# placa_eagle_1_1.net
KiCad netlist of a schematic drawn in EAGLE
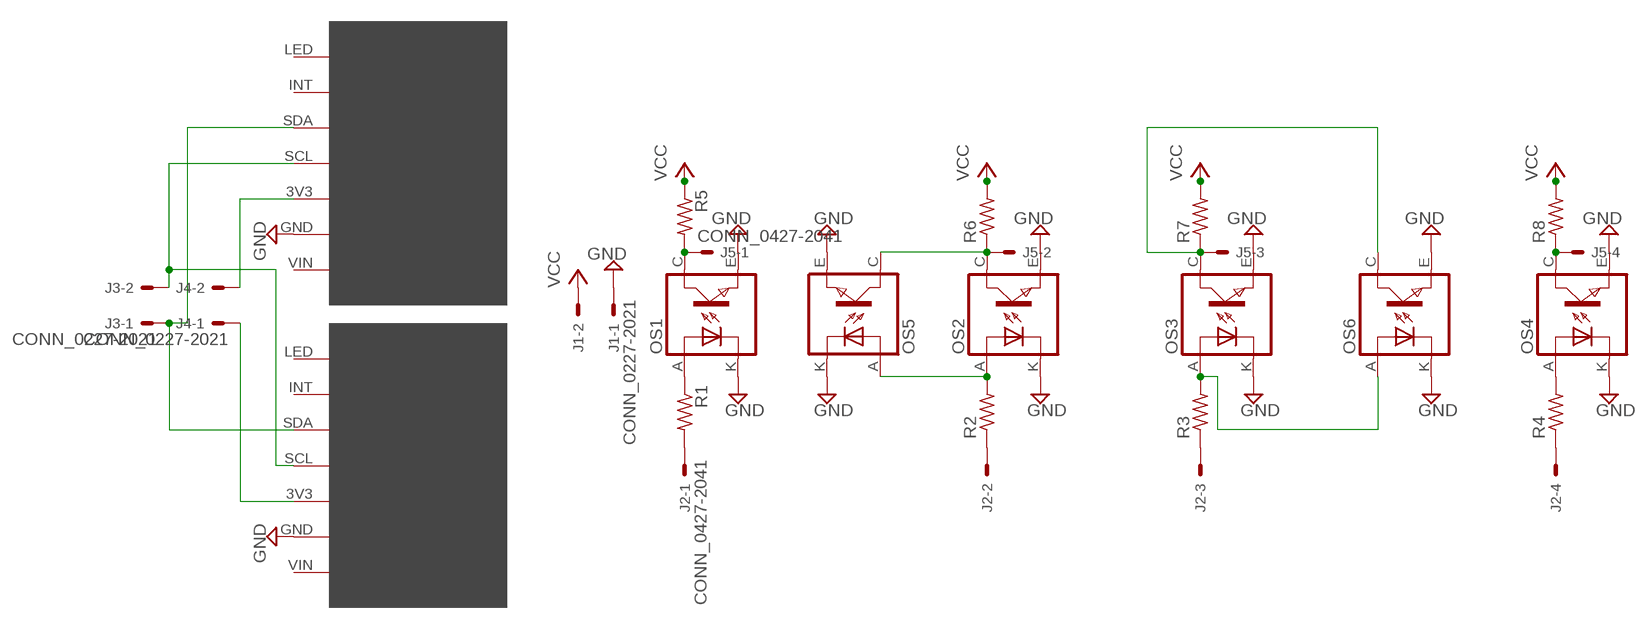
[diagram p0: schematic, sheet 1]

(export (version "E")
  (design (tool "Eeschema 10.0.6"))
  (components
    (comp (ref "J1")
      (value "CONN_0227-2021")
      (footprint "eagle-import:6410-02")
      (libsource (lib "eagle-import") (part "CONN_0227-2021"))
    )
    (comp (ref "J2")
      (value "CONN_0427-2041")
      (footprint "eagle-import:6410-04")
      (libsource (lib "eagle-import") (part "CONN_0427-2041"))
    )
    (comp (ref "J3")
      (value "CONN_0227-2021")
      (footprint "eagle-import:6410-02")
      (libsource (lib "eagle-import") (part "CONN_0227-2021"))
    )
    (comp (ref "J4")
      (value "CONN_0227-2021")
      (footprint "eagle-import:6410-02")
      (libsource (lib "eagle-import") (part "CONN_0227-2021"))
    )
    (comp (ref "J5")
      (value "CONN_0427-2041")
      (footprint "eagle-import:6410-04")
      (libsource (lib "eagle-import") (part "CONN_0427-2041"))
    )
    (comp (ref "OS1")
      (value "TCRT5000")
      (footprint "eagle-import:TCRT5000")
      (libsource (lib "eagle-import") (part "TCRT5000"))
    )
    (comp (ref "OS2")
      (value "TCRT5000")
      (footprint "eagle-import:TCRT5000")
      (libsource (lib "eagle-import") (part "TCRT5000"))
    )
    (comp (ref "OS3")
      (value "TCRT5000")
      (footprint "eagle-import:TCRT5000")
      (libsource (lib "eagle-import") (part "TCRT5000"))
    )
    (comp (ref "OS4")
      (value "TCRT5000")
      (footprint "eagle-import:TCRT5000")
      (libsource (lib "eagle-import") (part "TCRT5000"))
    )
    (comp (ref "OS5")
      (value "TCRT5000")
      (footprint "eagle-import:TCRT5000")
      (libsource (lib "eagle-import") (part "TCRT5000"))
    )
    (comp (ref "OS6")
      (value "TCRT5000")
      (footprint "eagle-import:TCRT5000")
      (libsource (lib "eagle-import") (part "TCRT5000"))
    )
    (comp (ref "R1")
      (value "R-US_0204/7")
      (footprint "eagle-import:0204_7")
      (libsource (lib "eagle-import") (part "R-US_0204/7"))
    )
    (comp (ref "R2")
      (value "R-US_0204/7")
      (footprint "eagle-import:0204_7")
      (libsource (lib "eagle-import") (part "R-US_0204/7"))
    )
    (comp (ref "R3")
      (value "R-US_0204/7")
      (footprint "eagle-import:0204_7")
      (libsource (lib "eagle-import") (part "R-US_0204/7"))
    )
    (comp (ref "R4")
      (value "R-US_0204/7")
      (footprint "eagle-import:0204_7")
      (libsource (lib "eagle-import") (part "R-US_0204/7"))
    )
    (comp (ref "R5")
      (value "R-US_0204/7")
      (footprint "eagle-import:0204_7")
      (libsource (lib "eagle-import") (part "R-US_0204/7"))
    )
    (comp (ref "R6")
      (value "R-US_0204/7")
      (footprint "eagle-import:0204_7")
      (libsource (lib "eagle-import") (part "R-US_0204/7"))
    )
    (comp (ref "R7")
      (value "R-US_0204/7")
      (footprint "eagle-import:0204_7")
      (libsource (lib "eagle-import") (part "R-US_0204/7"))
    )
    (comp (ref "R8")
      (value "R-US_0204/7")
      (footprint "eagle-import:0204_7")
      (libsource (lib "eagle-import") (part "R-US_0204/7"))
    )
    (comp (ref "TCS1")
      (value "TCS34725")
      (footprint "eagle-import:TCS34725")
      (libsource (lib "eagle-import") (part "TCS34725"))
    )
    (comp (ref "TCS2")
      (value "TCS34725")
      (footprint "eagle-import:TCS34725")
      (libsource (lib "eagle-import") (part "TCS34725"))
    )
  )
  (nets
    (net (code "1") (name "GND") (class "Default")
      (node (ref "J1") (pin "1") (pinfunction "S_1") (pintype "passive"))
      (node (ref "OS1") (pin "E") (pinfunction "EMITTER_E") (pintype "passive"))
      (node (ref "OS1") (pin "K") (pinfunction "CATHODE_K") (pintype "passive"))
      (node (ref "OS2") (pin "E") (pinfunction "EMITTER_E") (pintype "passive"))
      (node (ref "OS2") (pin "K") (pinfunction "CATHODE_K") (pintype "passive"))
      (node (ref "OS3") (pin "E") (pinfunction "EMITTER_E") (pintype "passive"))
      (node (ref "OS3") (pin "K") (pinfunction "CATHODE_K") (pintype "passive"))
      (node (ref "OS4") (pin "E") (pinfunction "EMITTER_E") (pintype "passive"))
      (node (ref "OS4") (pin "K") (pinfunction "CATHODE_K") (pintype "passive"))
      (node (ref "OS5") (pin "E") (pinfunction "EMITTER_E") (pintype "passive"))
      (node (ref "OS5") (pin "K") (pinfunction "CATHODE_K") (pintype "passive"))
      (node (ref "OS6") (pin "E") (pinfunction "EMITTER_E") (pintype "passive"))
      (node (ref "OS6") (pin "K") (pinfunction "CATHODE_K") (pintype "passive"))
      (node (ref "TCS1") (pin "GND") (pinfunction "GND_GND") (pintype "bidirectional"))
      (node (ref "TCS2") (pin "GND") (pinfunction "GND_GND") (pintype "bidirectional"))
    )
    (net (code "2") (name "Net-(J2A-S)") (class "Default")
      (node (ref "J2") (pin "1") (pinfunction "S_1") (pintype "passive"))
      (node (ref "R1") (pin "2") (pinfunction "2_2") (pintype "passive"))
    )
    (net (code "3") (name "Net-(J2B-S)") (class "Default")
      (node (ref "J2") (pin "2") (pinfunction "S_2") (pintype "passive"))
      (node (ref "R2") (pin "1") (pinfunction "1_1") (pintype "passive"))
    )
    (net (code "4") (name "Net-(J2C-S)") (class "Default")
      (node (ref "J2") (pin "3") (pinfunction "S_3") (pintype "passive"))
      (node (ref "R3") (pin "1") (pinfunction "1_1") (pintype "passive"))
    )
    (net (code "5") (name "Net-(J2D-S)") (class "Default")
      (node (ref "J2") (pin "4") (pinfunction "S_4") (pintype "passive"))
      (node (ref "R4") (pin "1") (pinfunction "1_1") (pintype "passive"))
    )
    (net (code "6") (name "Net-(J3A-S)") (class "Default")
      (node (ref "J3") (pin "1") (pinfunction "S_1") (pintype "passive"))
      (node (ref "TCS1") (pin "SDA") (pinfunction "SDA_SDA") (pintype "bidirectional"))
      (node (ref "TCS2") (pin "SDA") (pinfunction "SDA_SDA") (pintype "bidirectional"))
    )
    (net (code "7") (name "Net-(J3B-S)") (class "Default")
      (node (ref "J3") (pin "2") (pinfunction "S_2") (pintype "passive"))
      (node (ref "TCS1") (pin "SCL") (pinfunction "SCL_SCL") (pintype "bidirectional"))
      (node (ref "TCS2") (pin "SCL") (pinfunction "SCL_SCL") (pintype "bidirectional"))
    )
    (net (code "8") (name "Net-(J4A-S)") (class "Default")
      (node (ref "J4") (pin "1") (pinfunction "S_1") (pintype "passive"))
      (node (ref "TCS2") (pin "3V3") (pinfunction "3V3_3V3") (pintype "bidirectional"))
    )
    (net (code "9") (name "Net-(J4B-S)") (class "Default")
      (node (ref "J4") (pin "2") (pinfunction "S_2") (pintype "passive"))
      (node (ref "TCS1") (pin "3V3") (pinfunction "3V3_3V3") (pintype "bidirectional"))
    )
    (net (code "10") (name "Net-(J5A-S)") (class "Default")
      (node (ref "J5") (pin "1") (pinfunction "S_1") (pintype "passive"))
      (node (ref "OS1") (pin "C") (pinfunction "COLLECTOR_C") (pintype "passive"))
      (node (ref "R5") (pin "2") (pinfunction "2_2") (pintype "passive"))
    )
    (net (code "11") (name "Net-(J5B-S)") (class "Default")
      (node (ref "J5") (pin "2") (pinfunction "S_2") (pintype "passive"))
      (node (ref "OS2") (pin "C") (pinfunction "COLLECTOR_C") (pintype "passive"))
      (node (ref "OS5") (pin "C") (pinfunction "COLLECTOR_C") (pintype "passive"))
      (node (ref "R6") (pin "1") (pinfunction "1_1") (pintype "passive"))
    )
    (net (code "12") (name "Net-(J5C-S)") (class "Default")
      (node (ref "J5") (pin "3") (pinfunction "S_3") (pintype "passive"))
      (node (ref "OS3") (pin "C") (pinfunction "COLLECTOR_C") (pintype "passive"))
      (node (ref "OS6") (pin "C") (pinfunction "COLLECTOR_C") (pintype "passive"))
      (node (ref "R7") (pin "1") (pinfunction "1_1") (pintype "passive"))
    )
    (net (code "13") (name "Net-(J5D-S)") (class "Default")
      (node (ref "J5") (pin "4") (pinfunction "S_4") (pintype "passive"))
      (node (ref "OS4") (pin "C") (pinfunction "COLLECTOR_C") (pintype "passive"))
      (node (ref "R8") (pin "1") (pinfunction "1_1") (pintype "passive"))
    )
    (net (code "14") (name "Net-(OS1-ANODE)") (class "Default")
      (node (ref "OS1") (pin "A") (pinfunction "ANODE_A") (pintype "passive"))
      (node (ref "R1") (pin "1") (pinfunction "1_1") (pintype "passive"))
    )
    (net (code "15") (name "Net-(OS2-ANODE)") (class "Default")
      (node (ref "OS2") (pin "A") (pinfunction "ANODE_A") (pintype "passive"))
      (node (ref "OS5") (pin "A") (pinfunction "ANODE_A") (pintype "passive"))
      (node (ref "R2") (pin "2") (pinfunction "2_2") (pintype "passive"))
    )
    (net (code "16") (name "Net-(OS3-ANODE)") (class "Default")
      (node (ref "OS3") (pin "A") (pinfunction "ANODE_A") (pintype "passive"))
      (node (ref "OS6") (pin "A") (pinfunction "ANODE_A") (pintype "passive"))
      (node (ref "R3") (pin "2") (pinfunction "2_2") (pintype "passive"))
    )
    (net (code "17") (name "Net-(OS4-ANODE)") (class "Default")
      (node (ref "OS4") (pin "A") (pinfunction "ANODE_A") (pintype "passive"))
      (node (ref "R4") (pin "2") (pinfunction "2_2") (pintype "passive"))
    )
    (net (code "18") (name "VCC") (class "Default")
      (node (ref "J1") (pin "2") (pinfunction "S_2") (pintype "passive"))
      (node (ref "R5") (pin "1") (pinfunction "1_1") (pintype "passive"))
      (node (ref "R6") (pin "2") (pinfunction "2_2") (pintype "passive"))
      (node (ref "R7") (pin "2") (pinfunction "2_2") (pintype "passive"))
      (node (ref "R8") (pin "2") (pinfunction "2_2") (pintype "passive"))
    )
    (net (code "19") (name "unconnected-(TCS1-PadINT)") (class "Default")
      (node (ref "TCS1") (pin "INT") (pinfunction "INT_INT") (pintype "bidirectional"))
    )
    (net (code "20") (name "unconnected-(TCS1-PadLED)") (class "Default")
      (node (ref "TCS1") (pin "LED") (pinfunction "LED_LED") (pintype "bidirectional"))
    )
    (net (code "21") (name "unconnected-(TCS1-PadVIN)") (class "Default")
      (node (ref "TCS1") (pin "VIN") (pinfunction "VIN_VIN") (pintype "bidirectional"))
    )
    (net (code "22") (name "unconnected-(TCS2-PadINT)") (class "Default")
      (node (ref "TCS2") (pin "INT") (pinfunction "INT_INT") (pintype "bidirectional"))
    )
    (net (code "23") (name "unconnected-(TCS2-PadLED)") (class "Default")
      (node (ref "TCS2") (pin "LED") (pinfunction "LED_LED") (pintype "bidirectional"))
    )
    (net (code "24") (name "unconnected-(TCS2-PadVIN)") (class "Default")
      (node (ref "TCS2") (pin "VIN") (pinfunction "VIN_VIN") (pintype "bidirectional"))
    )
  )
)
